# tuch-tara-btr.net
KiCad netlist of a schematic drawn in Altium Designer
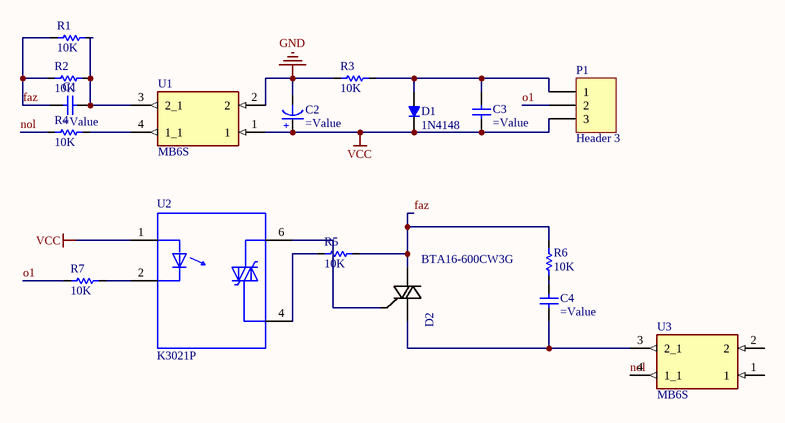
[diagram p0: tuch-tara-btr.SchDoc]

(export (version "E")
  (design (tool "Eeschema 10.0.6"))
  (components
    (comp (ref "C1")
      (value "~")
      (footprint "CAP-30")
      (description "Capacitor")
      (libsource (lib "AltiumLib1") (part "Capacitor"))
    )
    (comp (ref "C2")
      (value "~")
      (footprint "ELEC-CAP-RAD10-20")
      (description "Electrolytic Capacitor")
      (libsource (lib "AltiumLib1") (part "Capacitor Electrolytic"))
    )
    (comp (ref "C3")
      (value "~")
      (footprint "CAP 1206")
      (description "Capacitor")
      (libsource (lib "AltiumLib1") (part "Capacitor"))
    )
    (comp (ref "C4")
      (value "~")
      (footprint "CAP-30")
      (description "Capacitor")
      (libsource (lib "AltiumLib1") (part "Capacitor"))
    )
    (comp (ref "D1")
      (value "MODEL")
      (footprint "DO-41")
      (description "Diode")
      (fields (field (name "MODEL") "1N4148"))
      (libsource (lib "AltiumLib1") (part "Diode"))
    )
    (comp (ref "D2")
      (value "BTA16-600CW3G")
      (footprint "*TO254P1028X482X1968-3")
      (description "TRIAC Standard 600V 16A Through Hole TO-220AB")
      (fields (field (name "MF") "Littelfuse Inc."))
      (libsource (lib "BTA16-600CW3G") (part "BTA16-600CW3G"))
    )
    (comp (ref "P1")
      (value "Header 3")
      (footprint "HDR1X3")
      (description "Header, 3-Pin")
      (fields (field (name "PUBLISHER") "Altium Limited"))
      (libsource (lib "Miscellaneous Connectors") (part "Header 3"))
    )
    (comp (ref "R1")
      (value "10K")
      (footprint "RES 1206 (3216X08L)")
      (description "Resistor")
      (fields (field (name "TOLERANCE") "5%") (field (name "POWER") "1/4 W"))
      (libsource (lib "AltiumLib1") (part "Resistor"))
    )
    (comp (ref "R2")
      (value "10K")
      (footprint "Res-(1/4)")
      (description "Resistor")
      (fields (field (name "TOLERANCE") "5%") (field (name "POWER") "1/4 W"))
      (libsource (lib "AltiumLib1") (part "Resistor"))
    )
    (comp (ref "R3")
      (value "10K")
      (footprint "RES 1206 (3216X08L)")
      (description "Resistor")
      (fields (field (name "TOLERANCE") "5%") (field (name "POWER") "1/4 W"))
      (libsource (lib "AltiumLib1") (part "Resistor"))
    )
    (comp (ref "R4")
      (value "10K")
      (footprint "Res-(1/4)")
      (description "Resistor")
      (fields (field (name "TOLERANCE") "5%") (field (name "POWER") "1/4 W"))
      (libsource (lib "AltiumLib1") (part "Resistor"))
    )
    (comp (ref "R5")
      (value "10K")
      (footprint "RES 1206 (3216X08L)")
      (description "Resistor")
      (fields (field (name "TOLERANCE") "5%") (field (name "POWER") "1/4 W"))
      (libsource (lib "AltiumLib1") (part "Resistor"))
    )
    (comp (ref "R6")
      (value "10K")
      (footprint "RES 1206 (3216X08L)")
      (description "Resistor")
      (fields (field (name "TOLERANCE") "5%") (field (name "POWER") "1/4 W"))
      (libsource (lib "AltiumLib1") (part "Resistor"))
    )
    (comp (ref "R7")
      (value "10K")
      (footprint "RES 1206 (3216X08L)")
      (description "Resistor")
      (fields (field (name "TOLERANCE") "5%") (field (name "POWER") "1/4 W"))
      (libsource (lib "AltiumLib1") (part "Resistor"))
    )
    (comp (ref "U1")
      (value "MB6S")
      (footprint "SOIC245P670X270-4N")
      (description "Bridge Rectifier Single Phase Standard 600V Surface Mount 4-SOIC")
      (fields (field (name "MF") "ON Semiconductor") (field (name "DIGI-KEY_PART_NUMBER") "MB6SCT-ND"))
      (libsource (lib "MB6S") (part "MB6S"))
    )
    (comp (ref "U2")
      (value "K3021P")
      (footprint "DIP762W50P254L730H410Q6")
      (description "Optoisolator Triac Output 5300Vrms 1 Channel 6-DIP")
      (fields (field (name "MF") "Vishay Semiconductor"))
      (libsource (lib "K3021P") (part "K3021P"))
    )
    (comp (ref "U3")
      (value "MB6S")
      (footprint "SOIC245P670X270-4N")
      (description "Bridge Rectifier Single Phase Standard 600V Surface Mount 4-SOIC")
      (fields (field (name "MF") "ON Semiconductor") (field (name "DIGI-KEY_PART_NUMBER") "MB6SCT-ND"))
      (libsource (lib "MB6S") (part "MB6S"))
    )
  )
  (nets
    (net (code "1") (name "/faz") (class "Default")
      (node (ref "C1") (pin "1") (pinfunction "+_1") (pintype "passive"))
      (node (ref "D2") (pin "2") (pinfunction "MT2_2") (pintype "passive"))
      (node (ref "R1") (pin "2") (pinfunction "2_2") (pintype "passive"))
      (node (ref "R2") (pin "2") (pinfunction "2_2") (pintype "passive"))
      (node (ref "R5") (pin "2") (pinfunction "2_2") (pintype "passive"))
      (node (ref "R6") (pin "2") (pinfunction "2_2") (pintype "passive"))
    )
    (net (code "2") (name "/nol") (class "Default")
      (node (ref "R4") (pin "2") (pinfunction "2_2") (pintype "passive"))
      (node (ref "U3") (pin "4") (pinfunction "1_1_4") (pintype "output"))
    )
    (net (code "3") (name "/o1") (class "Default")
      (node (ref "P1") (pin "2") (pinfunction "2_2") (pintype "passive"))
      (node (ref "R7") (pin "1") (pinfunction "1_1") (pintype "passive"))
    )
    (net (code "4") (name "GND") (class "Default")
      (node (ref "C2") (pin "1") (pinfunction "-_1") (pintype "passive"))
      (node (ref "R3") (pin "2") (pinfunction "2_2") (pintype "passive"))
      (node (ref "U1") (pin "2") (pinfunction "2_2") (pintype "input"))
    )
    (net (code "5") (name "Net-(C1--)") (class "Default")
      (node (ref "C1") (pin "2") (pinfunction "-_2") (pintype "passive"))
      (node (ref "R1") (pin "1") (pinfunction "1_1") (pintype "passive"))
      (node (ref "R2") (pin "1") (pinfunction "1_1") (pintype "passive"))
      (node (ref "U1") (pin "3") (pinfunction "2_1_3") (pintype "output"))
    )
    (net (code "6") (name "Net-(C3--)") (class "Default")
      (node (ref "C3") (pin "2") (pinfunction "-_2") (pintype "passive"))
      (node (ref "D1") (pin "1") (pinfunction "A_1") (pintype "passive"))
      (node (ref "P1") (pin "1") (pinfunction "1_1") (pintype "passive"))
      (node (ref "R3") (pin "1") (pinfunction "1_1") (pintype "passive"))
    )
    (net (code "7") (name "Net-(C4-+)") (class "Default")
      (node (ref "C4") (pin "1") (pinfunction "+_1") (pintype "passive"))
      (node (ref "D2") (pin "1") (pinfunction "MT1_1") (pintype "passive"))
      (node (ref "U3") (pin "3") (pinfunction "2_1_3") (pintype "output"))
    )
    (net (code "8") (name "Net-(C4--)") (class "Default")
      (node (ref "C4") (pin "2") (pinfunction "-_2") (pintype "passive"))
      (node (ref "R6") (pin "1") (pinfunction "1_1") (pintype "passive"))
    )
    (net (code "9") (name "Net-(D2-G)") (class "Default")
      (node (ref "D2") (pin "3") (pinfunction "G_3") (pintype "passive"))
      (node (ref "U2") (pin "6") (pinfunction "MT2_6") (pintype "passive"))
    )
    (net (code "10") (name "Net-(U1-1_1)") (class "Default")
      (node (ref "R4") (pin "1") (pinfunction "1_1") (pintype "passive"))
      (node (ref "U1") (pin "4") (pinfunction "1_1_4") (pintype "output"))
    )
    (net (code "11") (name "Net-(U2-C)") (class "Default")
      (node (ref "R7") (pin "2") (pinfunction "2_2") (pintype "passive"))
      (node (ref "U2") (pin "2") (pinfunction "C_2") (pintype "passive"))
    )
    (net (code "12") (name "Net-(U2-MT1)") (class "Default")
      (node (ref "R5") (pin "1") (pinfunction "1_1") (pintype "passive"))
      (node (ref "U2") (pin "4") (pinfunction "MT1_4") (pintype "passive"))
    )
    (net (code "13") (name "VCC") (class "Default")
      (node (ref "C2") (pin "2") (pinfunction "+_2") (pintype "passive"))
      (node (ref "C3") (pin "1") (pinfunction "+_1") (pintype "passive"))
      (node (ref "D1") (pin "2") (pinfunction "K_2") (pintype "passive"))
      (node (ref "P1") (pin "3") (pinfunction "3_3") (pintype "passive"))
      (node (ref "U1") (pin "1") (pinfunction "1_1") (pintype "input"))
      (node (ref "U2") (pin "1") (pinfunction "A_1") (pintype "passive"))
    )
    (net (code "14") (name "unconnected-(U3-Pad1)") (class "Default")
      (node (ref "U3") (pin "1") (pinfunction "1_1") (pintype "input"))
    )
    (net (code "15") (name "unconnected-(U3-Pad2)") (class "Default")
      (node (ref "U3") (pin "2") (pinfunction "2_2") (pintype "input"))
    )
  )
)
